# Remote_Base.net
KiCad netlist of a schematic drawn in Altium Designer
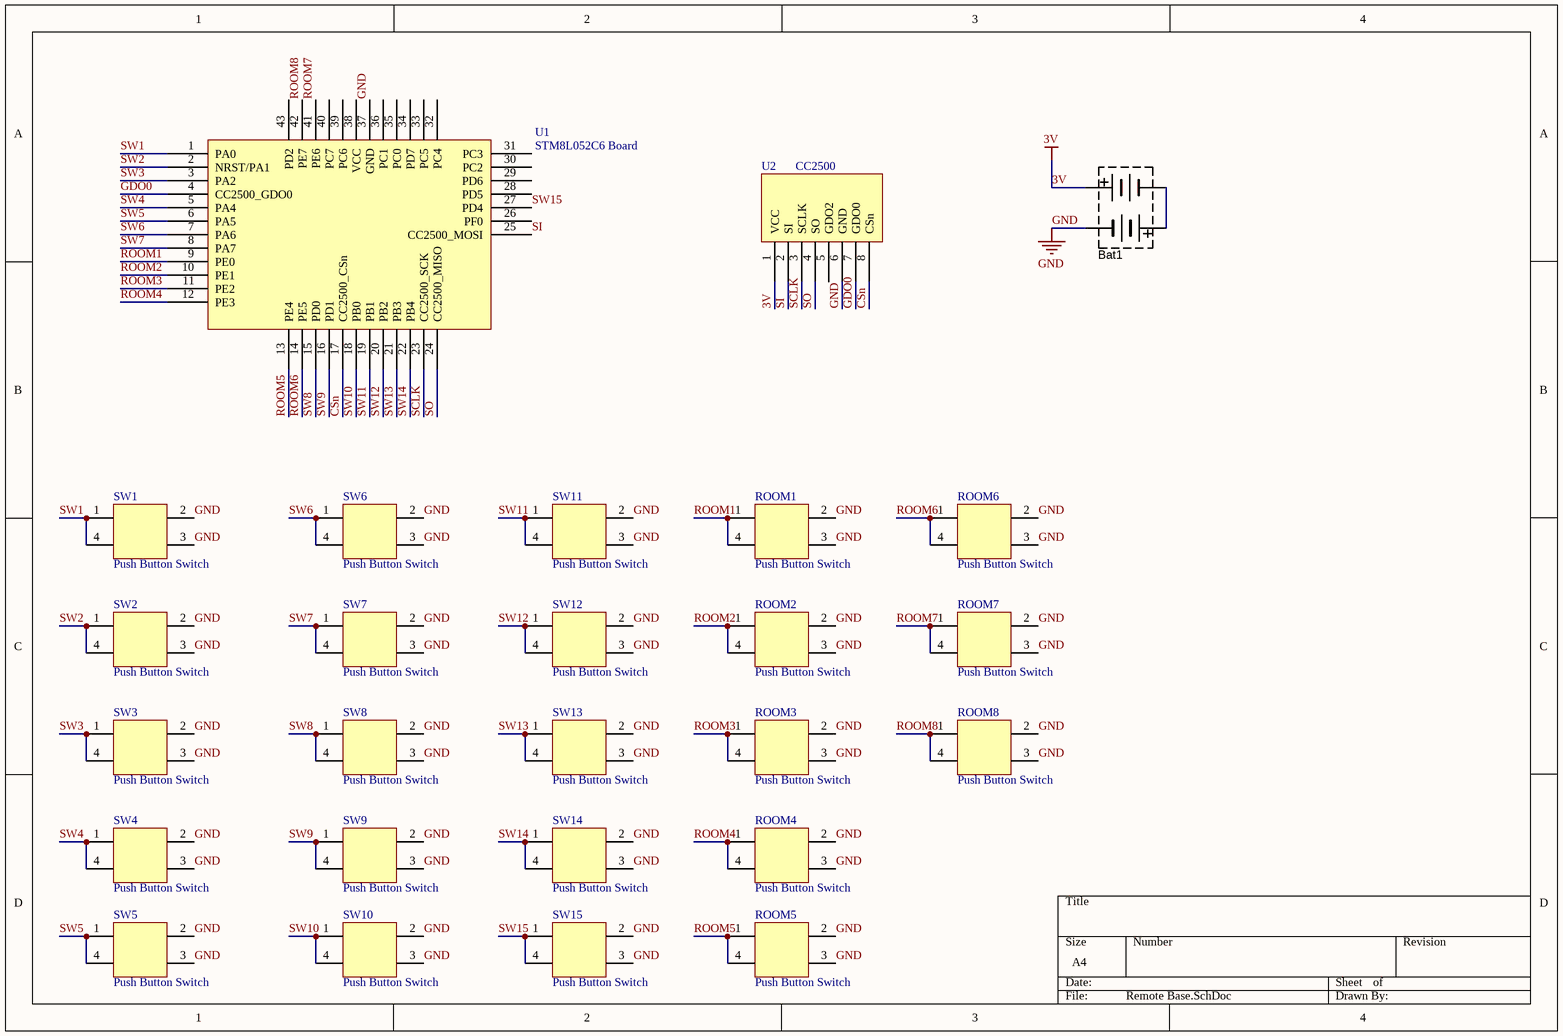
[diagram p0: Remote Base.SchDoc]

(export (version "E")
  (design (tool "Eeschema 10.0.6"))
  (components
    (comp (ref "Bat1")
      (value "NiMH-AA x 2")
      (footprint "BATT_HOLDER_2XAA")
      (description "Battery holder 2xAA PCB mount")
      (libsource (lib "All Packages") (part "BATT_AAx2_Holder"))
    )
    (comp (ref "ROOM1")
      (value "Push Button Switch")
      (footprint "Push Button Switch")
      (libsource (lib "Push Button Switch") (part "Push Button Switch"))
    )
    (comp (ref "ROOM2")
      (value "Push Button Switch")
      (footprint "Push Button Switch")
      (libsource (lib "Push Button Switch") (part "Push Button Switch"))
    )
    (comp (ref "ROOM3")
      (value "Push Button Switch")
      (footprint "Push Button Switch")
      (libsource (lib "Push Button Switch") (part "Push Button Switch"))
    )
    (comp (ref "ROOM4")
      (value "Push Button Switch")
      (footprint "Push Button Switch")
      (libsource (lib "Push Button Switch") (part "Push Button Switch"))
    )
    (comp (ref "ROOM5")
      (value "Push Button Switch")
      (footprint "Push Button Switch")
      (libsource (lib "Push Button Switch") (part "Push Button Switch"))
    )
    (comp (ref "ROOM6")
      (value "Push Button Switch")
      (footprint "Push Button Switch")
      (libsource (lib "Push Button Switch") (part "Push Button Switch"))
    )
    (comp (ref "ROOM7")
      (value "Push Button Switch")
      (footprint "Push Button Switch")
      (libsource (lib "Push Button Switch") (part "Push Button Switch"))
    )
    (comp (ref "ROOM8")
      (value "Push Button Switch")
      (footprint "Push Button Switch")
      (libsource (lib "Push Button Switch") (part "Push Button Switch"))
    )
    (comp (ref "SW1")
      (value "Push Button Switch")
      (footprint "Push Button Switch")
      (libsource (lib "Push Button Switch") (part "Push Button Switch"))
    )
    (comp (ref "SW2")
      (value "Push Button Switch")
      (footprint "Push Button Switch")
      (libsource (lib "Push Button Switch") (part "Push Button Switch"))
    )
    (comp (ref "SW3")
      (value "Push Button Switch")
      (footprint "Push Button Switch")
      (libsource (lib "Push Button Switch") (part "Push Button Switch"))
    )
    (comp (ref "SW4")
      (value "Push Button Switch")
      (footprint "Push Button Switch")
      (libsource (lib "Push Button Switch") (part "Push Button Switch"))
    )
    (comp (ref "SW5")
      (value "Push Button Switch")
      (footprint "Push Button Switch")
      (libsource (lib "Push Button Switch") (part "Push Button Switch"))
    )
    (comp (ref "SW6")
      (value "Push Button Switch")
      (footprint "Push Button Switch")
      (libsource (lib "Push Button Switch") (part "Push Button Switch"))
    )
    (comp (ref "SW7")
      (value "Push Button Switch")
      (footprint "Push Button Switch")
      (libsource (lib "Push Button Switch") (part "Push Button Switch"))
    )
    (comp (ref "SW8")
      (value "Push Button Switch")
      (footprint "Push Button Switch")
      (libsource (lib "Push Button Switch") (part "Push Button Switch"))
    )
    (comp (ref "SW9")
      (value "Push Button Switch")
      (footprint "Push Button Switch")
      (libsource (lib "Push Button Switch") (part "Push Button Switch"))
    )
    (comp (ref "SW10")
      (value "Push Button Switch")
      (footprint "Push Button Switch")
      (libsource (lib "Push Button Switch") (part "Push Button Switch"))
    )
    (comp (ref "SW11")
      (value "Push Button Switch")
      (footprint "Push Button Switch")
      (libsource (lib "Push Button Switch") (part "Push Button Switch"))
    )
    (comp (ref "SW12")
      (value "Push Button Switch")
      (footprint "Push Button Switch")
      (libsource (lib "Push Button Switch") (part "Push Button Switch"))
    )
    (comp (ref "SW13")
      (value "Push Button Switch")
      (footprint "Push Button Switch")
      (libsource (lib "Push Button Switch") (part "Push Button Switch"))
    )
    (comp (ref "SW14")
      (value "Push Button Switch")
      (footprint "Push Button Switch")
      (libsource (lib "Push Button Switch") (part "Push Button Switch"))
    )
    (comp (ref "SW15")
      (value "Push Button Switch")
      (footprint "Push Button Switch")
      (libsource (lib "Push Button Switch") (part "Push Button Switch"))
    )
    (comp (ref "U1")
      (value "STM8L052C6 Board")
      (footprint "STM8L052C6 BOARD")
      (libsource (lib "STM8L052C6 Board") (part "STM8L052C6 Board"))
    )
    (comp (ref "U2") (value "CC2500") (footprint "CC2500") (libsource (lib "CC2500") (part "CC2500")))
  )
  (nets
    (net (code "1") (name "/CSn") (class "Default")
      (node (ref "U1") (pin "17") (pinfunction "CC2500_CSn_17") (pintype "passive"))
      (node (ref "U2") (pin "8") (pinfunction "CSn_8") (pintype "passive"))
    )
    (net (code "2") (name "/GDO0") (class "Default")
      (node (ref "U1") (pin "4") (pinfunction "CC2500_GDO0_4") (pintype "passive"))
      (node (ref "U2") (pin "7") (pinfunction "GDO0_7") (pintype "passive"))
    )
    (net (code "3") (name "/ROOM1") (class "Default")
      (node (ref "ROOM1") (pin "1") (pintype "passive"))
      (node (ref "ROOM1") (pin "4") (pintype "passive"))
      (node (ref "U1") (pin "9") (pinfunction "PE0_9") (pintype "passive"))
    )
    (net (code "4") (name "/ROOM2") (class "Default")
      (node (ref "ROOM2") (pin "1") (pintype "passive"))
      (node (ref "ROOM2") (pin "4") (pintype "passive"))
      (node (ref "U1") (pin "10") (pinfunction "PE1_10") (pintype "passive"))
    )
    (net (code "5") (name "/ROOM3") (class "Default")
      (node (ref "ROOM3") (pin "1") (pintype "passive"))
      (node (ref "ROOM3") (pin "4") (pintype "passive"))
      (node (ref "U1") (pin "11") (pinfunction "PE2_11") (pintype "passive"))
    )
    (net (code "6") (name "/ROOM4") (class "Default")
      (node (ref "ROOM4") (pin "1") (pintype "passive"))
      (node (ref "ROOM4") (pin "4") (pintype "passive"))
      (node (ref "U1") (pin "12") (pinfunction "PE3_12") (pintype "passive"))
    )
    (net (code "7") (name "/ROOM5") (class "Default")
      (node (ref "ROOM5") (pin "1") (pintype "passive"))
      (node (ref "ROOM5") (pin "4") (pintype "passive"))
      (node (ref "U1") (pin "13") (pinfunction "PE4_13") (pintype "passive"))
    )
    (net (code "8") (name "/ROOM6") (class "Default")
      (node (ref "ROOM6") (pin "1") (pintype "passive"))
      (node (ref "ROOM6") (pin "4") (pintype "passive"))
      (node (ref "U1") (pin "14") (pinfunction "PE5_14") (pintype "passive"))
    )
    (net (code "9") (name "/ROOM7") (class "Default")
      (node (ref "ROOM7") (pin "1") (pintype "passive"))
      (node (ref "ROOM7") (pin "4") (pintype "passive"))
      (node (ref "U1") (pin "41") (pinfunction "PE6_41") (pintype "passive"))
    )
    (net (code "10") (name "/ROOM8") (class "Default")
      (node (ref "ROOM8") (pin "1") (pintype "passive"))
      (node (ref "ROOM8") (pin "4") (pintype "passive"))
      (node (ref "U1") (pin "42") (pinfunction "PE7_42") (pintype "passive"))
    )
    (net (code "11") (name "/SCLK") (class "Default")
      (node (ref "U1") (pin "23") (pinfunction "CC2500_SCK_23") (pintype "passive"))
      (node (ref "U2") (pin "3") (pinfunction "SCLK_3") (pintype "passive"))
    )
    (net (code "12") (name "/SI") (class "Default")
      (node (ref "U1") (pin "25") (pinfunction "CC2500_MOSI_25") (pintype "passive"))
      (node (ref "U2") (pin "2") (pinfunction "SI_2") (pintype "passive"))
    )
    (net (code "13") (name "/SO") (class "Default")
      (node (ref "U1") (pin "24") (pinfunction "CC2500_MISO_24") (pintype "passive"))
      (node (ref "U2") (pin "4") (pinfunction "SO_4") (pintype "passive"))
    )
    (net (code "14") (name "/SW1") (class "Default")
      (node (ref "SW1") (pin "1") (pintype "passive"))
      (node (ref "SW1") (pin "4") (pintype "passive"))
      (node (ref "U1") (pin "1") (pinfunction "PA0_1") (pintype "passive"))
    )
    (net (code "15") (name "/SW2") (class "Default")
      (node (ref "SW2") (pin "1") (pintype "passive"))
      (node (ref "SW2") (pin "4") (pintype "passive"))
      (node (ref "U1") (pin "2") (pinfunction "NRST/PA1_2") (pintype "passive"))
    )
    (net (code "16") (name "/SW3") (class "Default")
      (node (ref "SW3") (pin "1") (pintype "passive"))
      (node (ref "SW3") (pin "4") (pintype "passive"))
      (node (ref "U1") (pin "3") (pinfunction "PA2_3") (pintype "passive"))
    )
    (net (code "17") (name "/SW4") (class "Default")
      (node (ref "SW4") (pin "1") (pintype "passive"))
      (node (ref "SW4") (pin "4") (pintype "passive"))
      (node (ref "U1") (pin "5") (pinfunction "PA4_5") (pintype "passive"))
    )
    (net (code "18") (name "/SW5") (class "Default")
      (node (ref "SW5") (pin "1") (pintype "passive"))
      (node (ref "SW5") (pin "4") (pintype "passive"))
      (node (ref "U1") (pin "6") (pinfunction "PA5_6") (pintype "passive"))
    )
    (net (code "19") (name "/SW6") (class "Default")
      (node (ref "SW6") (pin "1") (pintype "passive"))
      (node (ref "SW6") (pin "4") (pintype "passive"))
      (node (ref "U1") (pin "7") (pinfunction "PA6_7") (pintype "passive"))
    )
    (net (code "20") (name "/SW7") (class "Default")
      (node (ref "SW7") (pin "1") (pintype "passive"))
      (node (ref "SW7") (pin "4") (pintype "passive"))
      (node (ref "U1") (pin "8") (pinfunction "PA7_8") (pintype "passive"))
    )
    (net (code "21") (name "/SW8") (class "Default")
      (node (ref "SW8") (pin "1") (pintype "passive"))
      (node (ref "SW8") (pin "4") (pintype "passive"))
      (node (ref "U1") (pin "15") (pinfunction "PD0_15") (pintype "passive"))
    )
    (net (code "22") (name "/SW9") (class "Default")
      (node (ref "SW9") (pin "1") (pintype "passive"))
      (node (ref "SW9") (pin "4") (pintype "passive"))
      (node (ref "U1") (pin "16") (pinfunction "PD1_16") (pintype "passive"))
    )
    (net (code "23") (name "/SW10") (class "Default")
      (node (ref "SW10") (pin "1") (pintype "passive"))
      (node (ref "SW10") (pin "4") (pintype "passive"))
      (node (ref "U1") (pin "18") (pinfunction "PB0_18") (pintype "passive"))
    )
    (net (code "24") (name "/SW11") (class "Default")
      (node (ref "SW11") (pin "1") (pintype "passive"))
      (node (ref "SW11") (pin "4") (pintype "passive"))
      (node (ref "U1") (pin "19") (pinfunction "PB1_19") (pintype "passive"))
    )
    (net (code "25") (name "/SW12") (class "Default")
      (node (ref "SW12") (pin "1") (pintype "passive"))
      (node (ref "SW12") (pin "4") (pintype "passive"))
      (node (ref "U1") (pin "20") (pinfunction "PB2_20") (pintype "passive"))
    )
    (net (code "26") (name "/SW13") (class "Default")
      (node (ref "SW13") (pin "1") (pintype "passive"))
      (node (ref "SW13") (pin "4") (pintype "passive"))
      (node (ref "U1") (pin "21") (pinfunction "PB3_21") (pintype "passive"))
    )
    (net (code "27") (name "/SW14") (class "Default")
      (node (ref "SW14") (pin "1") (pintype "passive"))
      (node (ref "SW14") (pin "4") (pintype "passive"))
      (node (ref "U1") (pin "22") (pinfunction "PB4_22") (pintype "passive"))
    )
    (net (code "28") (name "/SW15") (class "Default")
      (node (ref "SW15") (pin "1") (pintype "passive"))
      (node (ref "SW15") (pin "4") (pintype "passive"))
      (node (ref "U1") (pin "27") (pinfunction "PD4_27") (pintype "passive"))
    )
    (net (code "29") (name "3V") (class "Default")
      (node (ref "Bat1") (pin "C1+") (pinfunction "C1+_C1+") (pintype "passive"))
      (node (ref "U2") (pin "1") (pinfunction "VCC_1") (pintype "passive"))
    )
    (net (code "30") (name "GND") (class "Default")
      (node (ref "Bat1") (pin "C2-") (pinfunction "C2-_C2-") (pintype "passive"))
      (node (ref "ROOM1") (pin "2") (pintype "passive"))
      (node (ref "ROOM1") (pin "3") (pintype "passive"))
      (node (ref "ROOM2") (pin "2") (pintype "passive"))
      (node (ref "ROOM2") (pin "3") (pintype "passive"))
      (node (ref "ROOM3") (pin "2") (pintype "passive"))
      (node (ref "ROOM3") (pin "3") (pintype "passive"))
      (node (ref "ROOM4") (pin "2") (pintype "passive"))
      (node (ref "ROOM4") (pin "3") (pintype "passive"))
      (node (ref "ROOM5") (pin "2") (pintype "passive"))
      (node (ref "ROOM5") (pin "3") (pintype "passive"))
      (node (ref "ROOM6") (pin "2") (pintype "passive"))
      (node (ref "ROOM6") (pin "3") (pintype "passive"))
      (node (ref "ROOM7") (pin "2") (pintype "passive"))
      (node (ref "ROOM7") (pin "3") (pintype "passive"))
      (node (ref "ROOM8") (pin "2") (pintype "passive"))
      (node (ref "ROOM8") (pin "3") (pintype "passive"))
      (node (ref "SW1") (pin "2") (pintype "passive"))
      (node (ref "SW1") (pin "3") (pintype "passive"))
      (node (ref "SW10") (pin "2") (pintype "passive"))
      (node (ref "SW10") (pin "3") (pintype "passive"))
      (node (ref "SW11") (pin "2") (pintype "passive"))
      (node (ref "SW11") (pin "3") (pintype "passive"))
      (node (ref "SW12") (pin "2") (pintype "passive"))
      (node (ref "SW12") (pin "3") (pintype "passive"))
      (node (ref "SW13") (pin "2") (pintype "passive"))
      (node (ref "SW13") (pin "3") (pintype "passive"))
      (node (ref "SW14") (pin "2") (pintype "passive"))
      (node (ref "SW14") (pin "3") (pintype "passive"))
      (node (ref "SW15") (pin "2") (pintype "passive"))
      (node (ref "SW15") (pin "3") (pintype "passive"))
      (node (ref "SW2") (pin "2") (pintype "passive"))
      (node (ref "SW2") (pin "3") (pintype "passive"))
      (node (ref "SW3") (pin "2") (pintype "passive"))
      (node (ref "SW3") (pin "3") (pintype "passive"))
      (node (ref "SW4") (pin "2") (pintype "passive"))
      (node (ref "SW4") (pin "3") (pintype "passive"))
      (node (ref "SW5") (pin "2") (pintype "passive"))
      (node (ref "SW5") (pin "3") (pintype "passive"))
      (node (ref "SW6") (pin "2") (pintype "passive"))
      (node (ref "SW6") (pin "3") (pintype "passive"))
      (node (ref "SW7") (pin "2") (pintype "passive"))
      (node (ref "SW7") (pin "3") (pintype "passive"))
      (node (ref "SW8") (pin "2") (pintype "passive"))
      (node (ref "SW8") (pin "3") (pintype "passive"))
      (node (ref "SW9") (pin "2") (pintype "passive"))
      (node (ref "SW9") (pin "3") (pintype "passive"))
      (node (ref "U1") (pin "37") (pinfunction "GND_37") (pintype "passive"))
      (node (ref "U2") (pin "6") (pinfunction "GND_6") (pintype "passive"))
    )
    (net (code "31") (name "Net-(Bat1-PadC1-)") (class "Default")
      (node (ref "Bat1") (pin "C1-") (pinfunction "C1-_C1-") (pintype "passive"))
      (node (ref "Bat1") (pin "C2+") (pinfunction "C2+_C2+") (pintype "passive"))
    )
    (net (code "32") (name "unconnected-(U1-PC0-Pad35)") (class "Default")
      (node (ref "U1") (pin "35") (pinfunction "PC0_35") (pintype "passive"))
    )
    (net (code "33") (name "unconnected-(U1-PC1-Pad36)") (class "Default")
      (node (ref "U1") (pin "36") (pinfunction "PC1_36") (pintype "passive"))
    )
    (net (code "34") (name "unconnected-(U1-PC2-Pad30)") (class "Default")
      (node (ref "U1") (pin "30") (pinfunction "PC2_30") (pintype "passive"))
    )
    (net (code "35") (name "unconnected-(U1-PC3-Pad31)") (class "Default")
      (node (ref "U1") (pin "31") (pinfunction "PC3_31") (pintype "passive"))
    )
    (net (code "36") (name "unconnected-(U1-PC4-Pad32)") (class "Default")
      (node (ref "U1") (pin "32") (pinfunction "PC4_32") (pintype "passive"))
    )
    (net (code "37") (name "unconnected-(U1-PC5-Pad33)") (class "Default")
      (node (ref "U1") (pin "33") (pinfunction "PC5_33") (pintype "passive"))
    )
    (net (code "38") (name "unconnected-(U1-PC6-Pad39)") (class "Default")
      (node (ref "U1") (pin "39") (pinfunction "PC6_39") (pintype "passive"))
    )
    (net (code "39") (name "unconnected-(U1-PC7-Pad40)") (class "Default")
      (node (ref "U1") (pin "40") (pinfunction "PC7_40") (pintype "passive"))
    )
    (net (code "40") (name "unconnected-(U1-PD2-Pad43)") (class "Default")
      (node (ref "U1") (pin "43") (pinfunction "PD2_43") (pintype "passive"))
    )
    (net (code "41") (name "unconnected-(U1-PD5-Pad28)") (class "Default")
      (node (ref "U1") (pin "28") (pinfunction "PD5_28") (pintype "passive"))
    )
    (net (code "42") (name "unconnected-(U1-PD6-Pad29)") (class "Default")
      (node (ref "U1") (pin "29") (pinfunction "PD6_29") (pintype "passive"))
    )
    (net (code "43") (name "unconnected-(U1-PD7-Pad34)") (class "Default")
      (node (ref "U1") (pin "34") (pinfunction "PD7_34") (pintype "passive"))
    )
    (net (code "44") (name "unconnected-(U1-PF0-Pad26)") (class "Default")
      (node (ref "U1") (pin "26") (pinfunction "PF0_26") (pintype "passive"))
    )
    (net (code "45") (name "unconnected-(U1-VCC-Pad38)") (class "Default")
      (node (ref "U1") (pin "38") (pinfunction "VCC_38") (pintype "passive"))
    )
    (net (code "46") (name "unconnected-(U2-GDO2-Pad5)") (class "Default")
      (node (ref "U2") (pin "5") (pinfunction "GDO2_5") (pintype "passive"))
    )
  )
)
